# 3_3.net
KiCad netlist of a schematic drawn in Altium Designer
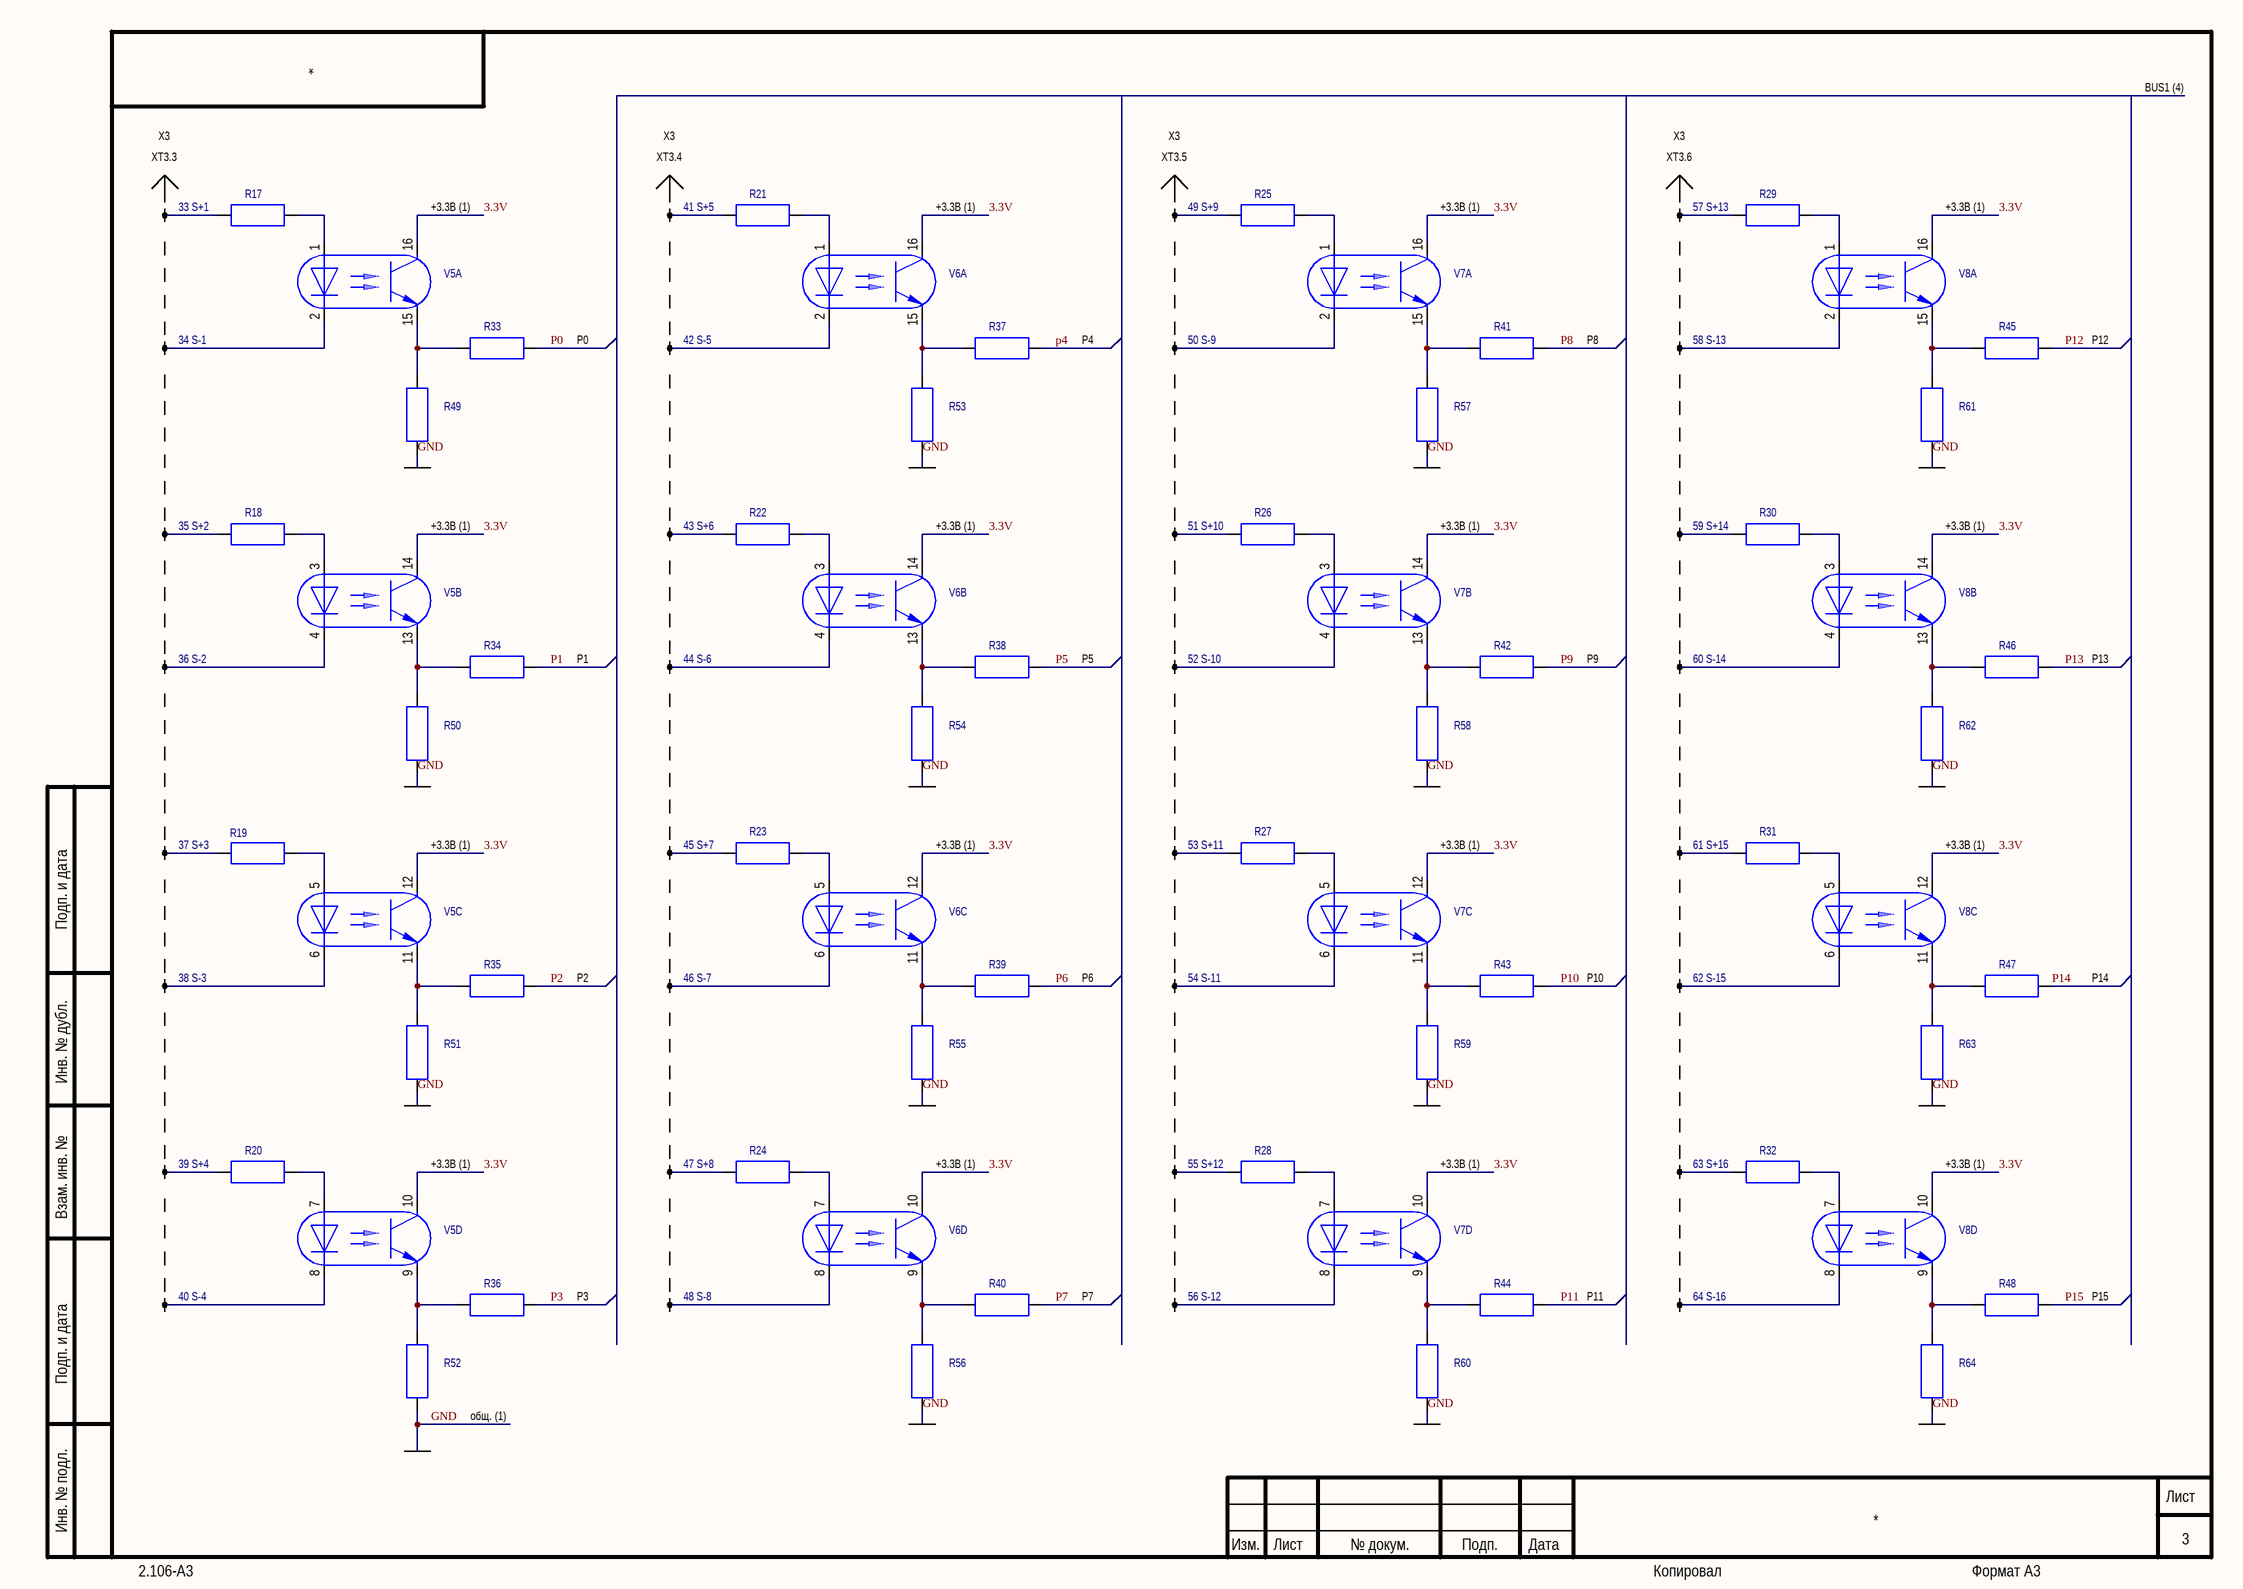
[diagram p0: Э3_3.SchDoc]

(export (version "E")
  (design (tool "Eeschema 10.0.6"))
  (components
    (comp (ref "R17") (value "380") (footprint "PcbLib1:RES0805") (libsource (lib "Schlib1") (part "R")))
    (comp (ref "R18") (value "380") (footprint "PcbLib1:RES0805") (libsource (lib "Schlib1") (part "R")))
    (comp (ref "R19") (value "380") (footprint "PcbLib1:RES0805") (libsource (lib "Schlib1") (part "R")))
    (comp (ref "R20") (value "380") (footprint "PcbLib1:RES0805") (libsource (lib "Schlib1") (part "R")))
    (comp (ref "R21") (value "380") (footprint "PcbLib1:RES0805") (libsource (lib "Schlib1") (part "R")))
    (comp (ref "R22") (value "380") (footprint "PcbLib1:RES0805") (libsource (lib "Schlib1") (part "R")))
    (comp (ref "R23") (value "380") (footprint "PcbLib1:RES0805") (libsource (lib "Schlib1") (part "R")))
    (comp (ref "R24") (value "380") (footprint "PcbLib1:RES0805") (libsource (lib "Schlib1") (part "R")))
    (comp (ref "R25") (value "380") (footprint "PcbLib1:RES0805") (libsource (lib "Schlib1") (part "R")))
    (comp (ref "R26") (value "380") (footprint "PcbLib1:RES0805") (libsource (lib "Schlib1") (part "R")))
    (comp (ref "R27") (value "380") (footprint "PcbLib1:RES0805") (libsource (lib "Schlib1") (part "R")))
    (comp (ref "R28") (value "380") (footprint "PcbLib1:RES0805") (libsource (lib "Schlib1") (part "R")))
    (comp (ref "R29") (value "380") (footprint "PcbLib1:RES0805") (libsource (lib "Schlib1") (part "R")))
    (comp (ref "R30") (value "380") (footprint "PcbLib1:RES0805") (libsource (lib "Schlib1") (part "R")))
    (comp (ref "R31") (value "380") (footprint "PcbLib1:RES0805") (libsource (lib "Schlib1") (part "R")))
    (comp (ref "R32") (value "380") (footprint "PcbLib1:RES0805") (libsource (lib "Schlib1") (part "R")))
    (comp (ref "R33") (value "10к") (footprint "PcbLib1:RES0805") (libsource (lib "Schlib1") (part "R")))
    (comp (ref "R34") (value "10к") (footprint "PcbLib1:RES0805") (libsource (lib "Schlib1") (part "R")))
    (comp (ref "R35") (value "10к") (footprint "PcbLib1:RES0805") (libsource (lib "Schlib1") (part "R")))
    (comp (ref "R36") (value "10к") (footprint "PcbLib1:RES0805") (libsource (lib "Schlib1") (part "R")))
    (comp (ref "R37") (value "10к") (footprint "PcbLib1:RES0805") (libsource (lib "Schlib1") (part "R")))
    (comp (ref "R38") (value "10к") (footprint "PcbLib1:RES0805") (libsource (lib "Schlib1") (part "R")))
    (comp (ref "R39") (value "10к") (footprint "PcbLib1:RES0805") (libsource (lib "Schlib1") (part "R")))
    (comp (ref "R40") (value "10к") (footprint "PcbLib1:RES0805") (libsource (lib "Schlib1") (part "R")))
    (comp (ref "R41") (value "10к") (footprint "PcbLib1:RES0805") (libsource (lib "Schlib1") (part "R")))
    (comp (ref "R42") (value "10к") (footprint "PcbLib1:RES0805") (libsource (lib "Schlib1") (part "R")))
    (comp (ref "R43") (value "10к") (footprint "PcbLib1:RES0805") (libsource (lib "Schlib1") (part "R")))
    (comp (ref "R44") (value "10к") (footprint "PcbLib1:RES0805") (libsource (lib "Schlib1") (part "R")))
    (comp (ref "R45") (value "10к") (footprint "PcbLib1:RES0805") (libsource (lib "Schlib1") (part "R")))
    (comp (ref "R46") (value "10к") (footprint "PcbLib1:RES0805") (libsource (lib "Schlib1") (part "R")))
    (comp (ref "R47") (value "10к") (footprint "PcbLib1:RES0805") (libsource (lib "Schlib1") (part "R")))
    (comp (ref "R48") (value "10к") (footprint "PcbLib1:RES0805") (libsource (lib "Schlib1") (part "R")))
    (comp (ref "R49") (value "1к") (footprint "PcbLib1:RES0805") (libsource (lib "Schlib1") (part "R")))
    (comp (ref "R50") (value "1к") (footprint "PcbLib1:RES0805") (libsource (lib "Schlib1") (part "R")))
    (comp (ref "R51") (value "1к") (footprint "PcbLib1:RES0805") (libsource (lib "Schlib1") (part "R")))
    (comp (ref "R52") (value "1к") (footprint "PcbLib1:RES0805") (libsource (lib "Schlib1") (part "R")))
    (comp (ref "R53") (value "1к") (footprint "PcbLib1:RES0805") (libsource (lib "Schlib1") (part "R")))
    (comp (ref "R54") (value "1к") (footprint "PcbLib1:RES0805") (libsource (lib "Schlib1") (part "R")))
    (comp (ref "R55") (value "1к") (footprint "PcbLib1:RES0805") (libsource (lib "Schlib1") (part "R")))
    (comp (ref "R56") (value "1к") (footprint "PcbLib1:RES0805") (libsource (lib "Schlib1") (part "R")))
    (comp (ref "R57") (value "1к") (footprint "PcbLib1:RES0805") (libsource (lib "Schlib1") (part "R")))
    (comp (ref "R58") (value "1к") (footprint "PcbLib1:RES0805") (libsource (lib "Schlib1") (part "R")))
    (comp (ref "R59") (value "1к") (footprint "PcbLib1:RES0805") (libsource (lib "Schlib1") (part "R")))
    (comp (ref "R60") (value "1к") (footprint "PcbLib1:RES0805") (libsource (lib "Schlib1") (part "R")))
    (comp (ref "R61") (value "1к") (footprint "PcbLib1:RES0805") (libsource (lib "Schlib1") (part "R")))
    (comp (ref "R62") (value "1к") (footprint "PcbLib1:RES0805") (libsource (lib "Schlib1") (part "R")))
    (comp (ref "R63") (value "1к") (footprint "PcbLib1:RES0805") (libsource (lib "Schlib1") (part "R")))
    (comp (ref "R64") (value "1к") (footprint "PcbLib1:RES0805") (libsource (lib "Schlib1") (part "R")))
    (comp (ref "V5")
      (value "ACPL247_1")
      (footprint "PcbLib1:SOP127P700X220-16N")
      (libsource (lib "Schlib1") (part "ACPL247_1"))
    )
    (comp (ref "V6")
      (value "ACPL247_1")
      (footprint "PcbLib1:SOP127P700X220-16N")
      (libsource (lib "Schlib1") (part "ACPL247_1"))
    )
    (comp (ref "V7")
      (value "ACPL247_1")
      (footprint "PcbLib1:SOP127P700X220-16N")
      (libsource (lib "Schlib1") (part "ACPL247_1"))
    )
    (comp (ref "V8")
      (value "ACPL247_1")
      (footprint "PcbLib1:SOP127P700X220-16N")
      (libsource (lib "Schlib1") (part "ACPL247_1"))
    )
    (comp (ref "X3") (value "33 S+1") (footprint "PcbLib1:PLD64") (libsource (lib "Schlib1") (part "PLD64")))
  )
  (nets
    (net (code "1") (name "/3.3V") (class "Default")
      (node (ref "V5") (pin "10") (pintype "passive"))
      (node (ref "V5") (pin "12") (pintype "passive"))
      (node (ref "V5") (pin "14") (pintype "passive"))
      (node (ref "V5") (pin "16") (pintype "passive"))
      (node (ref "V6") (pin "10") (pintype "passive"))
      (node (ref "V6") (pin "12") (pintype "passive"))
      (node (ref "V6") (pin "14") (pintype "passive"))
      (node (ref "V6") (pin "16") (pintype "passive"))
      (node (ref "V7") (pin "10") (pintype "passive"))
      (node (ref "V7") (pin "12") (pintype "passive"))
      (node (ref "V7") (pin "14") (pintype "passive"))
      (node (ref "V7") (pin "16") (pintype "passive"))
      (node (ref "V8") (pin "10") (pintype "passive"))
      (node (ref "V8") (pin "12") (pintype "passive"))
      (node (ref "V8") (pin "14") (pintype "passive"))
      (node (ref "V8") (pin "16") (pintype "passive"))
    )
    (net (code "2") (name "/GND") (class "Default")
      (node (ref "R49") (pin "1") (pintype "passive"))
      (node (ref "R50") (pin "1") (pintype "passive"))
      (node (ref "R51") (pin "1") (pintype "passive"))
      (node (ref "R52") (pin "1") (pintype "passive"))
      (node (ref "R53") (pin "1") (pintype "passive"))
      (node (ref "R54") (pin "1") (pintype "passive"))
      (node (ref "R55") (pin "1") (pintype "passive"))
      (node (ref "R56") (pin "1") (pintype "passive"))
      (node (ref "R57") (pin "1") (pintype "passive"))
      (node (ref "R58") (pin "1") (pintype "passive"))
      (node (ref "R59") (pin "1") (pintype "passive"))
      (node (ref "R60") (pin "1") (pintype "passive"))
      (node (ref "R61") (pin "1") (pintype "passive"))
      (node (ref "R62") (pin "1") (pintype "passive"))
      (node (ref "R63") (pin "1") (pintype "passive"))
      (node (ref "R64") (pin "1") (pintype "passive"))
    )
    (net (code "3") (name "/P0") (class "Default") (node (ref "R33") (pin "2") (pintype "passive")))
    (net (code "4") (name "/P1") (class "Default") (node (ref "R34") (pin "2") (pintype "passive")))
    (net (code "5") (name "/P2") (class "Default") (node (ref "R35") (pin "2") (pintype "passive")))
    (net (code "6") (name "/P3") (class "Default") (node (ref "R36") (pin "2") (pintype "passive")))
    (net (code "7") (name "/P5") (class "Default") (node (ref "R38") (pin "2") (pintype "passive")))
    (net (code "8") (name "/P6") (class "Default") (node (ref "R39") (pin "2") (pintype "passive")))
    (net (code "9") (name "/P7") (class "Default") (node (ref "R40") (pin "2") (pintype "passive")))
    (net (code "10") (name "/P8") (class "Default") (node (ref "R41") (pin "2") (pintype "passive")))
    (net (code "11") (name "/P9") (class "Default") (node (ref "R42") (pin "2") (pintype "passive")))
    (net (code "12") (name "/P10") (class "Default") (node (ref "R43") (pin "2") (pintype "passive")))
    (net (code "13") (name "/P11") (class "Default") (node (ref "R44") (pin "2") (pintype "passive")))
    (net (code "14") (name "/P12") (class "Default") (node (ref "R45") (pin "2") (pintype "passive")))
    (net (code "15") (name "/P13") (class "Default") (node (ref "R46") (pin "2") (pintype "passive")))
    (net (code "16") (name "/P14") (class "Default") (node (ref "R47") (pin "2") (pintype "passive")))
    (net (code "17") (name "/P15") (class "Default") (node (ref "R48") (pin "2") (pintype "passive")))
    (net (code "18") (name "/p4") (class "Default") (node (ref "R37") (pin "2") (pintype "passive")))
    (net (code "19") (name "Net-(R17-Pad2)") (class "Default")
      (node (ref "R17") (pin "2") (pintype "passive"))
      (node (ref "V5") (pin "1") (pintype "passive"))
    )
    (net (code "20") (name "Net-(R18-Pad2)") (class "Default")
      (node (ref "R18") (pin "2") (pintype "passive"))
      (node (ref "V5") (pin "3") (pintype "passive"))
    )
    (net (code "21") (name "Net-(R19-Pad2)") (class "Default")
      (node (ref "R19") (pin "2") (pintype "passive"))
      (node (ref "V5") (pin "5") (pintype "passive"))
    )
    (net (code "22") (name "Net-(R20-Pad2)") (class "Default")
      (node (ref "R20") (pin "2") (pintype "passive"))
      (node (ref "V5") (pin "7") (pintype "passive"))
    )
    (net (code "23") (name "Net-(R21-Pad2)") (class "Default")
      (node (ref "R21") (pin "2") (pintype "passive"))
      (node (ref "V6") (pin "1") (pintype "passive"))
    )
    (net (code "24") (name "Net-(R22-Pad2)") (class "Default")
      (node (ref "R22") (pin "2") (pintype "passive"))
      (node (ref "V6") (pin "3") (pintype "passive"))
    )
    (net (code "25") (name "Net-(R23-Pad2)") (class "Default")
      (node (ref "R23") (pin "2") (pintype "passive"))
      (node (ref "V6") (pin "5") (pintype "passive"))
    )
    (net (code "26") (name "Net-(R24-Pad2)") (class "Default")
      (node (ref "R24") (pin "2") (pintype "passive"))
      (node (ref "V6") (pin "7") (pintype "passive"))
    )
    (net (code "27") (name "Net-(R25-Pad2)") (class "Default")
      (node (ref "R25") (pin "2") (pintype "passive"))
      (node (ref "V7") (pin "1") (pintype "passive"))
    )
    (net (code "28") (name "Net-(R26-Pad2)") (class "Default")
      (node (ref "R26") (pin "2") (pintype "passive"))
      (node (ref "V7") (pin "3") (pintype "passive"))
    )
    (net (code "29") (name "Net-(R27-Pad2)") (class "Default")
      (node (ref "R27") (pin "2") (pintype "passive"))
      (node (ref "V7") (pin "5") (pintype "passive"))
    )
    (net (code "30") (name "Net-(R28-Pad2)") (class "Default")
      (node (ref "R28") (pin "2") (pintype "passive"))
      (node (ref "V7") (pin "7") (pintype "passive"))
    )
    (net (code "31") (name "Net-(R29-Pad2)") (class "Default")
      (node (ref "R29") (pin "2") (pintype "passive"))
      (node (ref "V8") (pin "1") (pintype "passive"))
    )
    (net (code "32") (name "Net-(R30-Pad2)") (class "Default")
      (node (ref "R30") (pin "2") (pintype "passive"))
      (node (ref "V8") (pin "3") (pintype "passive"))
    )
    (net (code "33") (name "Net-(R31-Pad2)") (class "Default")
      (node (ref "R31") (pin "2") (pintype "passive"))
      (node (ref "V8") (pin "5") (pintype "passive"))
    )
    (net (code "34") (name "Net-(R32-Pad2)") (class "Default")
      (node (ref "R32") (pin "2") (pintype "passive"))
      (node (ref "V8") (pin "7") (pintype "passive"))
    )
    (net (code "35") (name "Net-(R33-Pad1)") (class "Default")
      (node (ref "R33") (pin "1") (pintype "passive"))
      (node (ref "R49") (pin "2") (pintype "passive"))
      (node (ref "V5") (pin "15") (pintype "passive"))
    )
    (net (code "36") (name "Net-(R34-Pad1)") (class "Default")
      (node (ref "R34") (pin "1") (pintype "passive"))
      (node (ref "R50") (pin "2") (pintype "passive"))
      (node (ref "V5") (pin "13") (pintype "passive"))
    )
    (net (code "37") (name "Net-(R35-Pad1)") (class "Default")
      (node (ref "R35") (pin "1") (pintype "passive"))
      (node (ref "R51") (pin "2") (pintype "passive"))
      (node (ref "V5") (pin "11") (pintype "passive"))
    )
    (net (code "38") (name "Net-(R36-Pad1)") (class "Default")
      (node (ref "R36") (pin "1") (pintype "passive"))
      (node (ref "R52") (pin "2") (pintype "passive"))
      (node (ref "V5") (pin "9") (pintype "passive"))
    )
    (net (code "39") (name "Net-(R37-Pad1)") (class "Default")
      (node (ref "R37") (pin "1") (pintype "passive"))
      (node (ref "R53") (pin "2") (pintype "passive"))
      (node (ref "V6") (pin "15") (pintype "passive"))
    )
    (net (code "40") (name "Net-(R38-Pad1)") (class "Default")
      (node (ref "R38") (pin "1") (pintype "passive"))
      (node (ref "R54") (pin "2") (pintype "passive"))
      (node (ref "V6") (pin "13") (pintype "passive"))
    )
    (net (code "41") (name "Net-(R39-Pad1)") (class "Default")
      (node (ref "R39") (pin "1") (pintype "passive"))
      (node (ref "R55") (pin "2") (pintype "passive"))
      (node (ref "V6") (pin "11") (pintype "passive"))
    )
    (net (code "42") (name "Net-(R40-Pad1)") (class "Default")
      (node (ref "R40") (pin "1") (pintype "passive"))
      (node (ref "R56") (pin "2") (pintype "passive"))
      (node (ref "V6") (pin "9") (pintype "passive"))
    )
    (net (code "43") (name "Net-(R41-Pad1)") (class "Default")
      (node (ref "R41") (pin "1") (pintype "passive"))
      (node (ref "R57") (pin "2") (pintype "passive"))
      (node (ref "V7") (pin "15") (pintype "passive"))
    )
    (net (code "44") (name "Net-(R42-Pad1)") (class "Default")
      (node (ref "R42") (pin "1") (pintype "passive"))
      (node (ref "R58") (pin "2") (pintype "passive"))
      (node (ref "V7") (pin "13") (pintype "passive"))
    )
    (net (code "45") (name "Net-(R43-Pad1)") (class "Default")
      (node (ref "R43") (pin "1") (pintype "passive"))
      (node (ref "R59") (pin "2") (pintype "passive"))
      (node (ref "V7") (pin "11") (pintype "passive"))
    )
    (net (code "46") (name "Net-(R44-Pad1)") (class "Default")
      (node (ref "R44") (pin "1") (pintype "passive"))
      (node (ref "R60") (pin "2") (pintype "passive"))
      (node (ref "V7") (pin "9") (pintype "passive"))
    )
    (net (code "47") (name "Net-(R45-Pad1)") (class "Default")
      (node (ref "R45") (pin "1") (pintype "passive"))
      (node (ref "R61") (pin "2") (pintype "passive"))
      (node (ref "V8") (pin "15") (pintype "passive"))
    )
    (net (code "48") (name "Net-(R46-Pad1)") (class "Default")
      (node (ref "R46") (pin "1") (pintype "passive"))
      (node (ref "R62") (pin "2") (pintype "passive"))
      (node (ref "V8") (pin "13") (pintype "passive"))
    )
    (net (code "49") (name "Net-(R47-Pad1)") (class "Default")
      (node (ref "R47") (pin "1") (pintype "passive"))
      (node (ref "R63") (pin "2") (pintype "passive"))
      (node (ref "V8") (pin "11") (pintype "passive"))
    )
    (net (code "50") (name "Net-(R48-Pad1)") (class "Default")
      (node (ref "R48") (pin "1") (pintype "passive"))
      (node (ref "R64") (pin "2") (pintype "passive"))
      (node (ref "V8") (pin "9") (pintype "passive"))
    )
    (net (code "51") (name "Net-(X3AG-1)") (class "Default")
      (node (ref "R17") (pin "1") (pintype "passive"))
      (node (ref "X3") (pin "8") (pinfunction "1_8") (pintype "passive"))
    )
    (net (code "52") (name "Net-(X3AH-1)") (class "Default")
      (node (ref "V5") (pin "2") (pintype "passive"))
      (node (ref "X3") (pin "9") (pinfunction "1_9") (pintype "passive"))
    )
    (net (code "53") (name "Net-(X3AI-1)") (class "Default")
      (node (ref "R18") (pin "1") (pintype "passive"))
      (node (ref "X3") (pin "24") (pinfunction "1_24") (pintype "passive"))
    )
    (net (code "54") (name "Net-(X3AJ-1)") (class "Default")
      (node (ref "V5") (pin "4") (pintype "passive"))
      (node (ref "X3") (pin "27") (pinfunction "1_27") (pintype "passive"))
    )
    (net (code "55") (name "Net-(X3AK-1)") (class "Default")
      (node (ref "R19") (pin "1") (pintype "passive"))
      (node (ref "X3") (pin "28") (pinfunction "1_28") (pintype "passive"))
    )
    (net (code "56") (name "Net-(X3AL-1)") (class "Default")
      (node (ref "V5") (pin "6") (pintype "passive"))
      (node (ref "X3") (pin "29") (pinfunction "1_29") (pintype "passive"))
    )
    (net (code "57") (name "Net-(X3AM-1)") (class "Default")
      (node (ref "R20") (pin "1") (pintype "passive"))
      (node (ref "X3") (pin "30") (pinfunction "1_30") (pintype "passive"))
    )
    (net (code "58") (name "Net-(X3AN-1)") (class "Default")
      (node (ref "V5") (pin "8") (pintype "passive"))
      (node (ref "X3") (pin "31") (pinfunction "1_31") (pintype "passive"))
    )
    (net (code "59") (name "Net-(X3AO-1)") (class "Default")
      (node (ref "R21") (pin "1") (pintype "passive"))
      (node (ref "X3") (pin "33") (pinfunction "1_33") (pintype "passive"))
    )
    (net (code "60") (name "Net-(X3AP-1)") (class "Default")
      (node (ref "V6") (pin "2") (pintype "passive"))
      (node (ref "X3") (pin "35") (pinfunction "1_35") (pintype "passive"))
    )
    (net (code "61") (name "Net-(X3AQ-1)") (class "Default")
      (node (ref "R22") (pin "1") (pintype "passive"))
      (node (ref "X3") (pin "37") (pinfunction "1_37") (pintype "passive"))
    )
    (net (code "62") (name "Net-(X3AR-1)") (class "Default")
      (node (ref "V6") (pin "4") (pintype "passive"))
      (node (ref "X3") (pin "38") (pinfunction "1_38") (pintype "passive"))
    )
    (net (code "63") (name "Net-(X3AS-1)") (class "Default")
      (node (ref "R23") (pin "1") (pintype "passive"))
      (node (ref "X3") (pin "40") (pinfunction "1_40") (pintype "passive"))
    )
    (net (code "64") (name "Net-(X3AT-1)") (class "Default")
      (node (ref "V6") (pin "6") (pintype "passive"))
      (node (ref "X3") (pin "42") (pinfunction "1_42") (pintype "passive"))
    )
    (net (code "65") (name "Net-(X3AU-1)") (class "Default")
      (node (ref "R24") (pin "1") (pintype "passive"))
      (node (ref "X3") (pin "44") (pinfunction "1_44") (pintype "passive"))
    )
    (net (code "66") (name "Net-(X3AV-1)") (class "Default")
      (node (ref "V6") (pin "8") (pintype "passive"))
      (node (ref "X3") (pin "46") (pinfunction "1_46") (pintype "passive"))
    )
    (net (code "67") (name "Net-(X3AW-1)") (class "Default")
      (node (ref "R25") (pin "1") (pintype "passive"))
      (node (ref "X3") (pin "25") (pinfunction "1_25") (pintype "passive"))
    )
    (net (code "68") (name "Net-(X3AX-1)") (class "Default")
      (node (ref "V7") (pin "2") (pintype "passive"))
      (node (ref "X3") (pin "26") (pinfunction "1_26") (pintype "passive"))
    )
    (net (code "69") (name "Net-(X3AY-1)") (class "Default")
      (node (ref "R26") (pin "1") (pintype "passive"))
      (node (ref "X3") (pin "10") (pinfunction "1_10") (pintype "passive"))
    )
    (net (code "70") (name "Net-(X3AZ-1)") (class "Default")
      (node (ref "V7") (pin "4") (pintype "passive"))
      (node (ref "X3") (pin "11") (pinfunction "1_11") (pintype "passive"))
    )
    (net (code "71") (name "Net-(X3BA-1)") (class "Default")
      (node (ref "R27") (pin "1") (pintype "passive"))
      (node (ref "X3") (pin "12") (pinfunction "1_12") (pintype "passive"))
    )
    (net (code "72") (name "Net-(X3BB-1)") (class "Default")
      (node (ref "V7") (pin "6") (pintype "passive"))
      (node (ref "X3") (pin "13") (pinfunction "1_13") (pintype "passive"))
    )
    (net (code "73") (name "Net-(X3BC-1)") (class "Default")
      (node (ref "R28") (pin "1") (pintype "passive"))
      (node (ref "X3") (pin "14") (pinfunction "1_14") (pintype "passive"))
    )
    (net (code "74") (name "Net-(X3BD-1)") (class "Default")
      (node (ref "V7") (pin "8") (pintype "passive"))
      (node (ref "X3") (pin "15") (pinfunction "1_15") (pintype "passive"))
    )
    (net (code "75") (name "Net-(X3BE-1)") (class "Default")
      (node (ref "R29") (pin "1") (pintype "passive"))
      (node (ref "X3") (pin "16") (pinfunction "1_16") (pintype "passive"))
    )
    (net (code "76") (name "Net-(X3BF-1)") (class "Default")
      (node (ref "V8") (pin "2") (pintype "passive"))
      (node (ref "X3") (pin "17") (pinfunction "1_17") (pintype "passive"))
    )
    (net (code "77") (name "Net-(X3BG-1)") (class "Default")
      (node (ref "R30") (pin "1") (pintype "passive"))
      (node (ref "X3") (pin "18") (pinfunction "1_18") (pintype "passive"))
    )
    (net (code "78") (name "Net-(X3BH-1)") (class "Default")
      (node (ref "V8") (pin "4") (pintype "passive"))
      (node (ref "X3") (pin "19") (pinfunction "1_19") (pintype "passive"))
    )
    (net (code "79") (name "Net-(X3BI-1)") (class "Default")
      (node (ref "R31") (pin "1") (pintype "passive"))
      (node (ref "X3") (pin "20") (pinfunction "1_20") (pintype "passive"))
    )
    (net (code "80") (name "Net-(X3BJ-1)") (class "Default")
      (node (ref "V8") (pin "6") (pintype "passive"))
      (node (ref "X3") (pin "21") (pinfunction "1_21") (pintype "passive"))
    )
    (net (code "81") (name "Net-(X3BK-1)") (class "Default")
      (node (ref "R32") (pin "1") (pintype "passive"))
      (node (ref "X3") (pin "22") (pinfunction "1_22") (pintype "passive"))
    )
    (net (code "82") (name "Net-(X3BL-1)") (class "Default")
      (node (ref "V8") (pin "8") (pintype "passive"))
      (node (ref "X3") (pin "23") (pinfunction "1_23") (pintype "passive"))
    )
  )
)
